# N-P-MOSFET-RG_adapter.net
KiCad netlist of a schematic drawn in EAGLE
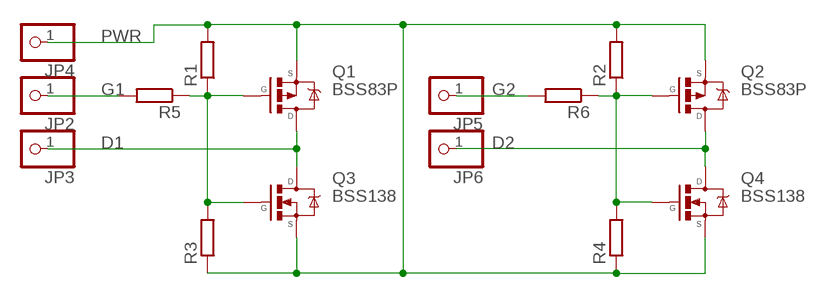
[diagram p0: schematic, sheet 1]

(export (version "E")
  (design (tool "Eeschema 10.0.6"))
  (components
    (comp (ref "JP2")
      (value "PINHD-1X1JUST_PIN")
      (footprint "eagle-import:1X01_BARE")
      (libsource (lib "eagle-import") (part "PINHD-1X1JUST_PIN"))
    )
    (comp (ref "JP3")
      (value "PINHD-1X1JUST_PIN")
      (footprint "eagle-import:1X01_BARE")
      (libsource (lib "eagle-import") (part "PINHD-1X1JUST_PIN"))
    )
    (comp (ref "JP4")
      (value "PINHD-1X1JUST_PIN")
      (footprint "eagle-import:1X01_BARE")
      (libsource (lib "eagle-import") (part "PINHD-1X1JUST_PIN"))
    )
    (comp (ref "JP5")
      (value "PINHD-1X1JUST_PIN")
      (footprint "eagle-import:1X01_BARE")
      (libsource (lib "eagle-import") (part "PINHD-1X1JUST_PIN"))
    )
    (comp (ref "JP6")
      (value "PINHD-1X1JUST_PIN")
      (footprint "eagle-import:1X01_BARE")
      (libsource (lib "eagle-import") (part "PINHD-1X1JUST_PIN"))
    )
    (comp (ref "Q1")
      (value "BSS83P")
      (footprint "eagle-import:SOT23")
      (libsource (lib "eagle-import") (part "BSS83P"))
    )
    (comp (ref "Q2")
      (value "BSS83P")
      (footprint "eagle-import:SOT23")
      (libsource (lib "eagle-import") (part "BSS83P"))
    )
    (comp (ref "Q3")
      (value "BSS138")
      (footprint "eagle-import:SOT23")
      (libsource (lib "eagle-import") (part "BSS138"))
    )
    (comp (ref "Q4")
      (value "BSS138")
      (footprint "eagle-import:SOT23")
      (libsource (lib "eagle-import") (part "BSS138"))
    )
    (comp (ref "R1")
      (value "R-EU_R0805")
      (footprint "eagle-import:R0805")
      (libsource (lib "eagle-import") (part "R-EU_R0805"))
    )
    (comp (ref "R2")
      (value "R-EU_R0805")
      (footprint "eagle-import:R0805")
      (libsource (lib "eagle-import") (part "R-EU_R0805"))
    )
    (comp (ref "R3")
      (value "R-EU_R0805")
      (footprint "eagle-import:R0805")
      (libsource (lib "eagle-import") (part "R-EU_R0805"))
    )
    (comp (ref "R4")
      (value "R-EU_R0805")
      (footprint "eagle-import:R0805")
      (libsource (lib "eagle-import") (part "R-EU_R0805"))
    )
    (comp (ref "R5")
      (value "R-EU_R0805")
      (footprint "eagle-import:R0805")
      (libsource (lib "eagle-import") (part "R-EU_R0805"))
    )
    (comp (ref "R6")
      (value "R-EU_R0805")
      (footprint "eagle-import:R0805")
      (libsource (lib "eagle-import") (part "R-EU_R0805"))
    )
  )
  (nets
    (net (code "1") (name "/D1") (class "Default")
      (node (ref "JP3") (pin "1") (pinfunction "1_1") (pintype "passive"))
      (node (ref "Q1") (pin "3") (pinfunction "D_3") (pintype "passive"))
      (node (ref "Q3") (pin "3") (pinfunction "D_3") (pintype "passive"))
    )
    (net (code "2") (name "/D2") (class "Default")
      (node (ref "JP6") (pin "1") (pinfunction "1_1") (pintype "passive"))
      (node (ref "Q2") (pin "3") (pinfunction "D_3") (pintype "passive"))
      (node (ref "Q4") (pin "3") (pinfunction "D_3") (pintype "passive"))
    )
    (net (code "3") (name "/G1") (class "Default")
      (node (ref "JP2") (pin "1") (pinfunction "1_1") (pintype "passive"))
      (node (ref "R5") (pin "2") (pinfunction "2_2") (pintype "passive"))
    )
    (net (code "4") (name "/G2") (class "Default")
      (node (ref "JP5") (pin "1") (pinfunction "1_1") (pintype "passive"))
      (node (ref "R6") (pin "2") (pinfunction "2_2") (pintype "passive"))
    )
    (net (code "5") (name "/PWR") (class "Default")
      (node (ref "JP4") (pin "1") (pinfunction "1_1") (pintype "passive"))
      (node (ref "Q1") (pin "2") (pinfunction "S_2") (pintype "passive"))
      (node (ref "Q2") (pin "2") (pinfunction "S_2") (pintype "passive"))
      (node (ref "Q3") (pin "2") (pinfunction "S_2") (pintype "passive"))
      (node (ref "Q4") (pin "2") (pinfunction "S_2") (pintype "passive"))
      (node (ref "R1") (pin "2") (pinfunction "2_2") (pintype "passive"))
      (node (ref "R2") (pin "2") (pinfunction "2_2") (pintype "passive"))
      (node (ref "R3") (pin "1") (pinfunction "1_1") (pintype "passive"))
      (node (ref "R4") (pin "1") (pinfunction "1_1") (pintype "passive"))
    )
    (net (code "6") (name "Net-(Q1-G)") (class "Default")
      (node (ref "Q1") (pin "1") (pinfunction "G_1") (pintype "passive"))
      (node (ref "Q3") (pin "1") (pinfunction "G_1") (pintype "passive"))
      (node (ref "R1") (pin "1") (pinfunction "1_1") (pintype "passive"))
      (node (ref "R3") (pin "2") (pinfunction "2_2") (pintype "passive"))
      (node (ref "R5") (pin "1") (pinfunction "1_1") (pintype "passive"))
    )
    (net (code "7") (name "Net-(Q2-G)") (class "Default")
      (node (ref "Q2") (pin "1") (pinfunction "G_1") (pintype "passive"))
      (node (ref "Q4") (pin "1") (pinfunction "G_1") (pintype "passive"))
      (node (ref "R2") (pin "1") (pinfunction "1_1") (pintype "passive"))
      (node (ref "R4") (pin "2") (pinfunction "2_2") (pintype "passive"))
      (node (ref "R6") (pin "1") (pinfunction "1_1") (pintype "passive"))
    )
  )
)
